# Microcontroller.net
KiCad netlist of a schematic drawn in Altium Designer
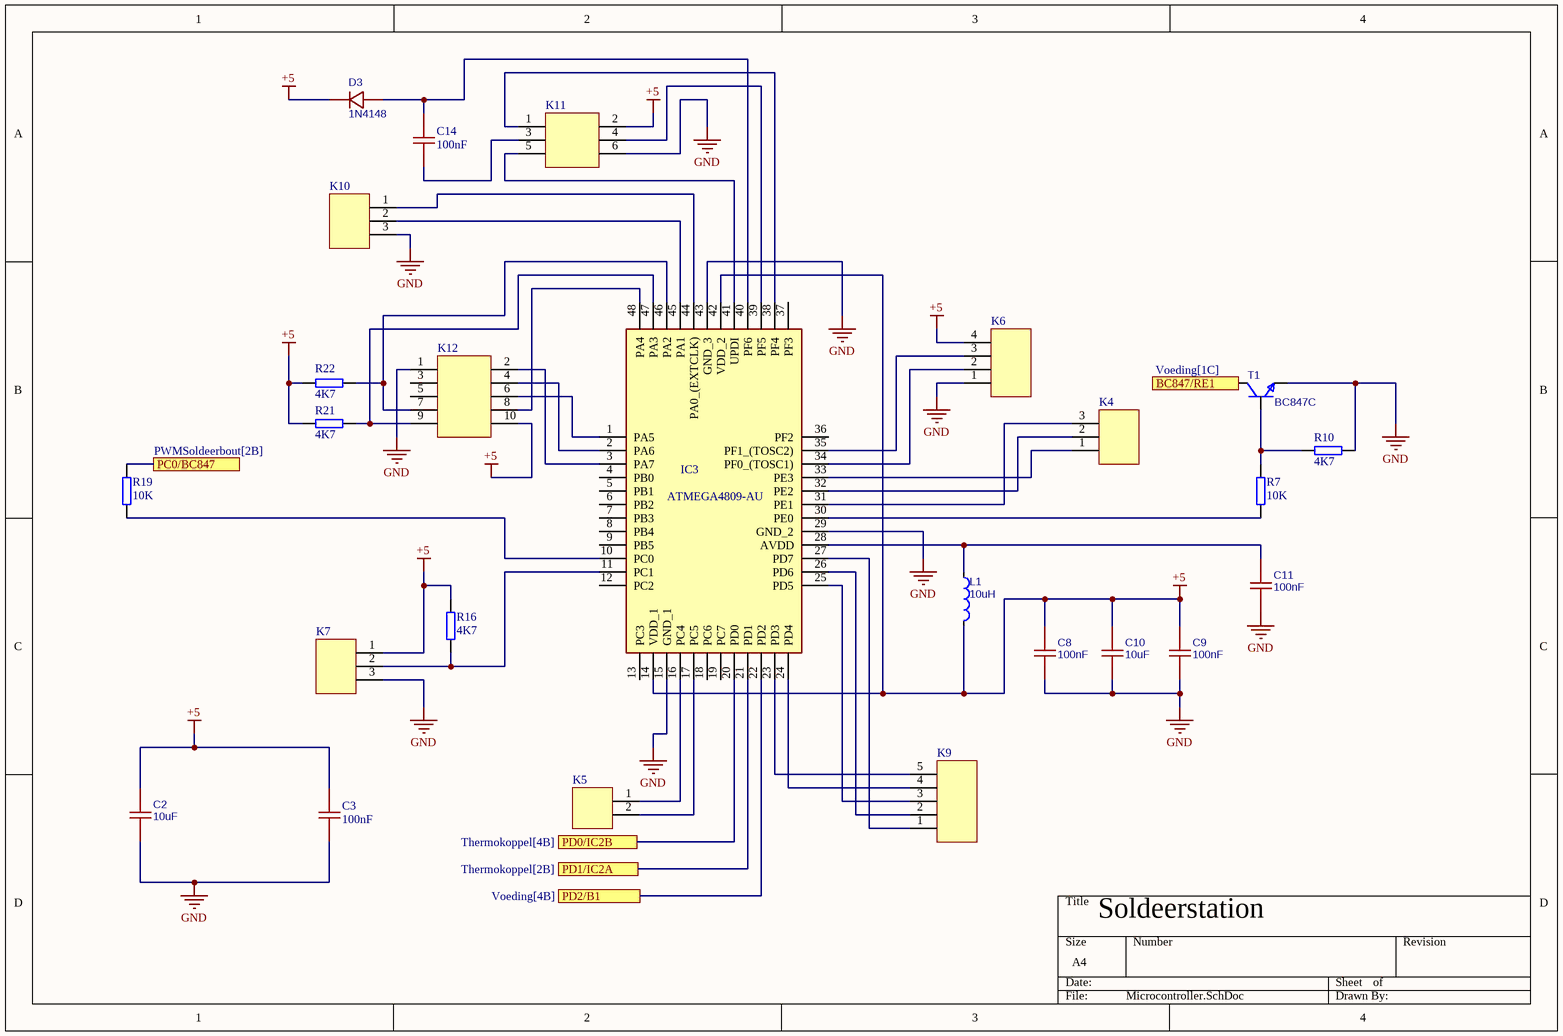
[diagram p0: Microcontroller.SchDoc]

(export (version "E")
  (design (tool "Eeschema 10.0.6"))
  (components
    (comp (ref "C2")
      (value "10uF")
      (footprint "C2,5,10 10uF")
      (fields
        (field (name "BOM_SUPPLIER PART") "C440198")
        (field (name "BOM_MANUFACTURER PART") "GRM21BR61H106KE43L")
        (field (name "CONTRIBUTOR") "LCSC")
      )
      (libsource (lib "SoldeerStation") (part "C2,5,10 10uF"))
    )
    (comp (ref "C3")
      (value "100nF")
      (footprint "C6,7,12,13 10nF")
      (libsource (lib "SoldeerStation") (part "C 100nF"))
    )
    (comp (ref "C8")
      (value "100nF")
      (footprint "C6,7,12,13 10nF")
      (fields
        (field (name "BOM_SUPPLIER PART") "C376921")
        (field (name "BOM_MANUFACTURER PART") "TCC0805X7R103M500DT")
        (field (name "CONTRIBUTOR") "LCSC")
      )
      (libsource (lib "SoldeerStation") (part "C6,7,12,13 10nF"))
    )
    (comp (ref "C9")
      (value "100nF")
      (footprint "C6,7,12,13 10nF")
      (fields
        (field (name "BOM_SUPPLIER PART") "C376921")
        (field (name "BOM_MANUFACTURER PART") "TCC0805X7R103M500DT")
        (field (name "CONTRIBUTOR") "LCSC")
      )
      (libsource (lib "SoldeerStation") (part "C6,7,12,13 10nF"))
    )
    (comp (ref "C10")
      (value "10uF")
      (footprint "C2,5,10 10uF")
      (fields
        (field (name "BOM_SUPPLIER PART") "C440198")
        (field (name "BOM_MANUFACTURER PART") "GRM21BR61H106KE43L")
        (field (name "CONTRIBUTOR") "LCSC")
      )
      (libsource (lib "SoldeerStation") (part "C2,5,10 10uF"))
    )
    (comp (ref "C11")
      (value "100nF")
      (footprint "C6,7,12,13 10nF")
      (fields
        (field (name "BOM_SUPPLIER PART") "C376921")
        (field (name "BOM_MANUFACTURER PART") "TCC0805X7R103M500DT")
        (field (name "CONTRIBUTOR") "LCSC")
      )
      (libsource (lib "SoldeerStation") (part "C6,7,12,13 10nF"))
    )
    (comp (ref "C14")
      (value "100nF")
      (footprint "C6,7,12,13 10nF")
      (libsource (lib "SoldeerStation") (part "C 100nF"))
    )
    (comp (ref "D3")
      (value "1N4148")
      (footprint "D3 1N14148")
      (description "1N4148W-C84367")
      (fields (field (name "BOM_MANUFACTURER PART") "1N4148W") (field (name "BOM_SUPPLIER PART") "C84367"))
      (libsource (lib "SoldeerStation") (part "D3 1N14148"))
    )
    (comp (ref "IC3")
      (value "ATMEGA4809-AU")
      (footprint "IC3 ATMEGA4809-AU")
      (description "8-bit Microcontrollers - MCU 20MHz, 48KB, TQFP")
      (fields (field (name "MOUSER PART NUMBER") "556-ATMEGA4809-AU"))
      (libsource (lib "SoldeerStation") (part "IC3 ATMEGA4809-AU"))
    )
    (comp (ref "K4") (value "~") (footprint "PInHeader_3") (libsource (lib "") (part "K PinHeader_3_1")))
    (comp (ref "K5")
      (value "~")
      (footprint "PInHeader_2")
      (libsource (lib "SoldeerStation") (part "K PinHeader_2"))
    )
    (comp (ref "K6")
      (value "~")
      (footprint "PInHeader_4")
      (libsource (lib "SoldeerStation") (part "K PinHeader_4"))
    )
    (comp (ref "K7")
      (value "~")
      (footprint "PInHeader_3")
      (libsource (lib "SoldeerStation") (part "K PinHeader_3"))
    )
    (comp (ref "K9")
      (value "~")
      (footprint "PInHeader_5")
      (libsource (lib "SoldeerStation") (part "K PinHeader_5"))
    )
    (comp (ref "K10")
      (value "~")
      (footprint "PInHeader_3")
      (libsource (lib "SoldeerStation") (part "K PinHeader_3"))
    )
    (comp (ref "K11")
      (value "~")
      (footprint "PInHeader_6")
      (libsource (lib "SoldeerStation") (part "K PinHeader_6"))
    )
    (comp (ref "K12")
      (value "~")
      (footprint "BOxHeader_10")
      (libsource (lib "SoldeerStation") (part "K Boxheader_10"))
    )
    (comp (ref "L1")
      (value "10uH")
      (footprint "L2 SmoorSpoel")
      (fields
        (field (name "BOM_SUPPLIER PART") "C2922559")
        (field (name "BOM_MANUFACTURER PART") "PMI201214S-100M")
        (field (name "CONTRIBUTOR") "LCSC")
      )
      (libsource (lib "SoldeerStation") (part "L2 smoorspoel"))
    )
    (comp (ref "R7")
      (value "10K")
      (footprint "RESC2013X50X30ML20T20")
      (fields (field (name "MANUFACTURER") "Vishay Dale") (field (name "PART NUMBER") "CRCW08050000Z0EA"))
      (libsource (lib "SoldeerStation") (part "R Resistor"))
    )
    (comp (ref "R10")
      (value "4K7")
      (footprint "RESC2013X50X30ML20T20")
      (fields (field (name "MANUFACTURER") "Vishay Dale") (field (name "PART NUMBER") "CRCW08050000Z0EA"))
      (libsource (lib "SoldeerStation") (part "R Resistor"))
    )
    (comp (ref "R16")
      (value "4K7")
      (footprint "RESC2013X50X30ML20T20")
      (fields (field (name "MANUFACTURER") "Vishay Dale") (field (name "PART NUMBER") "CRCW08050000Z0EA"))
      (libsource (lib "SoldeerStation") (part "R Resistor"))
    )
    (comp (ref "R19")
      (value "10K")
      (footprint "RESC2013X50X30ML20T20")
      (fields (field (name "MANUFACTURER") "Vishay Dale") (field (name "PART NUMBER") "CRCW08050000Z0EA"))
      (libsource (lib "SoldeerStation") (part "R Resistor"))
    )
    (comp (ref "R21")
      (value "4K7")
      (footprint "RESC2013X50X30ML20T20")
      (fields (field (name "MANUFACTURER") "Vishay Dale") (field (name "PART NUMBER") "CRCW08050000Z0EA"))
      (libsource (lib "SoldeerStation") (part "R Resistor"))
    )
    (comp (ref "R22")
      (value "4K7")
      (footprint "RESC2013X50X30ML20T20")
      (fields (field (name "MANUFACTURER") "Vishay Dale") (field (name "PART NUMBER") "CRCW08050000Z0EA"))
      (libsource (lib "SoldeerStation") (part "R Resistor"))
    )
    (comp (ref "T1")
      (value "BC847C")
      (footprint "T1,2,4 Bipolar Transistors")
      (description "BC847C_C3027113")
      (fields (field (name "BOM_SUPPLIER PART") "C3027113") (field (name "CONTRIBUTOR") "lcsc"))
      (libsource (lib "SoldeerStation") (part "T1,2,4 transisitors"))
    )
  )
  (nets
    (net (code "1") (name "+5") (class "Default")
      (node (ref "C10") (pin "2") (pinfunction "2_2") (pintype "passive"))
      (node (ref "C2") (pin "2") (pinfunction "2_2") (pintype "passive"))
      (node (ref "C3") (pin "2") (pinfunction "2_2") (pintype "passive"))
      (node (ref "C8") (pin "1") (pinfunction "1_1") (pintype "passive"))
      (node (ref "C9") (pin "1") (pinfunction "1_1") (pintype "passive"))
      (node (ref "D3") (pin "1") (pinfunction "C_1") (pintype "passive"))
      (node (ref "IC3") (pin "14") (pinfunction "VDD_1_14") (pintype "passive"))
      (node (ref "IC3") (pin "42") (pinfunction "VDD_2_42") (pintype "passive"))
      (node (ref "K11") (pin "2") (pintype "passive"))
      (node (ref "K12") (pin "10") (pintype "passive"))
      (node (ref "K6") (pin "4") (pintype "passive"))
      (node (ref "K7") (pin "1") (pintype "passive"))
      (node (ref "L1") (pin "2") (pinfunction "2_2") (pintype "passive"))
      (node (ref "R16") (pin "2") (pinfunction "2_2") (pintype "passive"))
      (node (ref "R21") (pin "1") (pinfunction "1_1") (pintype "passive"))
      (node (ref "R22") (pin "1") (pinfunction "1_1") (pintype "passive"))
    )
    (net (code "3") (name "/PC0{slash}BC847") (class "Default")
      (node (ref "R19") (pin "2") (pinfunction "2_2") (pintype "passive"))
    )
    (net (code "4") (name "/PD0{slash}IC2B") (class "Default")
      (node (ref "IC3") (pin "20") (pinfunction "PD0_20") (pintype "passive"))
    )
    (net (code "5") (name "/PD1{slash}IC2A") (class "Default")
      (node (ref "IC3") (pin "21") (pinfunction "PD1_21") (pintype "passive"))
    )
    (net (code "6") (name "/PD2{slash}B1") (class "Default")
      (node (ref "IC3") (pin "22") (pinfunction "PD2_22") (pintype "passive"))
    )
    (net (code "7") (name "GND") (class "Default")
      (node (ref "C10") (pin "1") (pinfunction "1_1") (pintype "passive"))
      (node (ref "C11") (pin "2") (pinfunction "2_2") (pintype "passive"))
      (node (ref "C2") (pin "1") (pinfunction "1_1") (pintype "passive"))
      (node (ref "C3") (pin "1") (pinfunction "1_1") (pintype "passive"))
      (node (ref "C8") (pin "2") (pinfunction "2_2") (pintype "passive"))
      (node (ref "C9") (pin "2") (pinfunction "2_2") (pintype "passive"))
      (node (ref "IC3") (pin "15") (pinfunction "GND_1_15") (pintype "passive"))
      (node (ref "IC3") (pin "29") (pinfunction "GND_2_29") (pintype "passive"))
      (node (ref "IC3") (pin "43") (pinfunction "GND_3_43") (pintype "passive"))
      (node (ref "K10") (pin "3") (pintype "passive"))
      (node (ref "K11") (pin "6") (pintype "passive"))
      (node (ref "K12") (pin "1") (pintype "passive"))
      (node (ref "K6") (pin "1") (pintype "passive"))
      (node (ref "K7") (pin "3") (pintype "passive"))
      (node (ref "R10") (pin "2") (pinfunction "2_2") (pintype "passive"))
      (node (ref "T1") (pin "2") (pinfunction "E_2") (pintype "passive"))
    )
    (net (code "8") (name "Net-(C14-Pad1)") (class "Default")
      (node (ref "C14") (pin "1") (pinfunction "1_1") (pintype "passive"))
      (node (ref "K11") (pin "3") (pintype "passive"))
    )
    (net (code "9") (name "Net-(D3-A)") (class "Default")
      (node (ref "C14") (pin "2") (pinfunction "2_2") (pintype "passive"))
      (node (ref "D3") (pin "2") (pinfunction "A_2") (pintype "passive"))
      (node (ref "IC3") (pin "40") (pinfunction "PF6_40") (pintype "passive"))
    )
    (net (code "10") (name "Net-(IC3-AVDD)") (class "Default")
      (node (ref "C11") (pin "1") (pinfunction "1_1") (pintype "passive"))
      (node (ref "IC3") (pin "28") (pinfunction "AVDD_28") (pintype "passive"))
      (node (ref "L1") (pin "1") (pinfunction "1_1") (pintype "passive"))
    )
    (net (code "11") (name "Net-(IC3-PA0_(EXTCLK))") (class "Default")
      (node (ref "IC3") (pin "44") (pinfunction "PA0_(EXTCLK)_44") (pintype "passive"))
      (node (ref "K10") (pin "1") (pintype "passive"))
    )
    (net (code "12") (name "Net-(IC3-PA1)") (class "Default")
      (node (ref "IC3") (pin "45") (pinfunction "PA1_45") (pintype "passive"))
      (node (ref "K10") (pin "2") (pintype "passive"))
    )
    (net (code "13") (name "Net-(IC3-PA2)") (class "Default")
      (node (ref "IC3") (pin "46") (pinfunction "PA2_46") (pintype "passive"))
      (node (ref "K12") (pin "7") (pintype "passive"))
      (node (ref "R22") (pin "2") (pinfunction "2_2") (pintype "passive"))
    )
    (net (code "14") (name "Net-(IC3-PA3)") (class "Default")
      (node (ref "IC3") (pin "47") (pinfunction "PA3_47") (pintype "passive"))
      (node (ref "K12") (pin "9") (pintype "passive"))
      (node (ref "R21") (pin "2") (pinfunction "2_2") (pintype "passive"))
    )
    (net (code "15") (name "Net-(IC3-PA4)") (class "Default")
      (node (ref "IC3") (pin "48") (pinfunction "PA4_48") (pintype "passive"))
      (node (ref "K12") (pin "8") (pintype "passive"))
    )
    (net (code "16") (name "Net-(IC3-PA5)") (class "Default")
      (node (ref "IC3") (pin "1") (pinfunction "PA5_1") (pintype "passive"))
      (node (ref "K12") (pin "6") (pintype "passive"))
    )
    (net (code "17") (name "Net-(IC3-PA6)") (class "Default")
      (node (ref "IC3") (pin "2") (pinfunction "PA6_2") (pintype "passive"))
      (node (ref "K12") (pin "4") (pintype "passive"))
    )
    (net (code "18") (name "Net-(IC3-PA7)") (class "Default")
      (node (ref "IC3") (pin "3") (pinfunction "PA7_3") (pintype "passive"))
      (node (ref "K12") (pin "2") (pintype "passive"))
    )
    (net (code "19") (name "Net-(IC3-PC0)") (class "Default")
      (node (ref "IC3") (pin "10") (pinfunction "PC0_10") (pintype "passive"))
      (node (ref "R19") (pin "1") (pinfunction "1_1") (pintype "passive"))
    )
    (net (code "20") (name "Net-(IC3-PC1)") (class "Default")
      (node (ref "IC3") (pin "11") (pinfunction "PC1_11") (pintype "passive"))
      (node (ref "K7") (pin "2") (pintype "passive"))
      (node (ref "R16") (pin "1") (pinfunction "1_1") (pintype "passive"))
    )
    (net (code "21") (name "Net-(IC3-PC4)") (class "Default")
      (node (ref "IC3") (pin "16") (pinfunction "PC4_16") (pintype "passive"))
      (node (ref "K5") (pin "1") (pintype "passive"))
    )
    (net (code "22") (name "Net-(IC3-PC5)") (class "Default")
      (node (ref "IC3") (pin "17") (pinfunction "PC5_17") (pintype "passive"))
      (node (ref "K5") (pin "2") (pintype "passive"))
    )
    (net (code "23") (name "Net-(IC3-PD3)") (class "Default")
      (node (ref "IC3") (pin "23") (pinfunction "PD3_23") (pintype "passive"))
      (node (ref "K9") (pin "5") (pintype "passive"))
    )
    (net (code "24") (name "Net-(IC3-PD4)") (class "Default")
      (node (ref "IC3") (pin "24") (pinfunction "PD4_24") (pintype "passive"))
      (node (ref "K9") (pin "4") (pintype "passive"))
    )
    (net (code "25") (name "Net-(IC3-PD5)") (class "Default")
      (node (ref "IC3") (pin "25") (pinfunction "PD5_25") (pintype "passive"))
      (node (ref "K9") (pin "3") (pintype "passive"))
    )
    (net (code "26") (name "Net-(IC3-PD6)") (class "Default")
      (node (ref "IC3") (pin "26") (pinfunction "PD6_26") (pintype "passive"))
      (node (ref "K9") (pin "2") (pintype "passive"))
    )
    (net (code "27") (name "Net-(IC3-PD7)") (class "Default")
      (node (ref "IC3") (pin "27") (pinfunction "PD7_27") (pintype "passive"))
      (node (ref "K9") (pin "1") (pintype "passive"))
    )
    (net (code "28") (name "Net-(IC3-PE0)") (class "Default")
      (node (ref "IC3") (pin "30") (pinfunction "PE0_30") (pintype "passive"))
      (node (ref "R7") (pin "1") (pinfunction "1_1") (pintype "passive"))
    )
    (net (code "29") (name "Net-(IC3-PE1)") (class "Default")
      (node (ref "IC3") (pin "31") (pinfunction "PE1_31") (pintype "passive"))
      (node (ref "K4") (pin "3") (pintype "passive"))
    )
    (net (code "30") (name "Net-(IC3-PE2)") (class "Default")
      (node (ref "IC3") (pin "32") (pinfunction "PE2_32") (pintype "passive"))
      (node (ref "K4") (pin "2") (pintype "passive"))
    )
    (net (code "31") (name "Net-(IC3-PE3)") (class "Default")
      (node (ref "IC3") (pin "33") (pinfunction "PE3_33") (pintype "passive"))
      (node (ref "K4") (pin "1") (pintype "passive"))
    )
    (net (code "32") (name "Net-(IC3-PF0_(TOSC1))") (class "Default")
      (node (ref "IC3") (pin "34") (pinfunction "PF0_(TOSC1)_34") (pintype "passive"))
      (node (ref "K6") (pin "2") (pintype "passive"))
    )
    (net (code "33") (name "Net-(IC3-PF1_(TOSC2))") (class "Default")
      (node (ref "IC3") (pin "35") (pinfunction "PF1_(TOSC2)_35") (pintype "passive"))
      (node (ref "K6") (pin "3") (pintype "passive"))
    )
    (net (code "34") (name "Net-(IC3-PF4)") (class "Default")
      (node (ref "IC3") (pin "38") (pinfunction "PF4_38") (pintype "passive"))
      (node (ref "K11") (pin "1") (pintype "passive"))
    )
    (net (code "35") (name "Net-(IC3-PF5)") (class "Default")
      (node (ref "IC3") (pin "39") (pinfunction "PF5_39") (pintype "passive"))
      (node (ref "K11") (pin "4") (pintype "passive"))
    )
    (net (code "36") (name "Net-(IC3-UPDI)") (class "Default")
      (node (ref "IC3") (pin "41") (pinfunction "UPDI_41") (pintype "passive"))
      (node (ref "K11") (pin "5") (pintype "passive"))
    )
    (net (code "37") (name "Net-(T1-B)") (class "Default")
      (node (ref "R10") (pin "1") (pinfunction "1_1") (pintype "passive"))
      (node (ref "R7") (pin "2") (pinfunction "2_2") (pintype "passive"))
      (node (ref "T1") (pin "1") (pinfunction "B_1") (pintype "passive"))
    )
    (net (code "38") (name "unconnected-(IC3-PB0-Pad4)") (class "Default")
      (node (ref "IC3") (pin "4") (pinfunction "PB0_4") (pintype "passive"))
    )
    (net (code "39") (name "unconnected-(IC3-PB1-Pad5)") (class "Default")
      (node (ref "IC3") (pin "5") (pinfunction "PB1_5") (pintype "passive"))
    )
    (net (code "40") (name "unconnected-(IC3-PB2-Pad6)") (class "Default")
      (node (ref "IC3") (pin "6") (pinfunction "PB2_6") (pintype "passive"))
    )
    (net (code "41") (name "unconnected-(IC3-PB3-Pad7)") (class "Default")
      (node (ref "IC3") (pin "7") (pinfunction "PB3_7") (pintype "passive"))
    )
    (net (code "42") (name "unconnected-(IC3-PB4-Pad8)") (class "Default")
      (node (ref "IC3") (pin "8") (pinfunction "PB4_8") (pintype "passive"))
    )
    (net (code "43") (name "unconnected-(IC3-PB5-Pad9)") (class "Default")
      (node (ref "IC3") (pin "9") (pinfunction "PB5_9") (pintype "passive"))
    )
    (net (code "44") (name "unconnected-(IC3-PC2-Pad12)") (class "Default")
      (node (ref "IC3") (pin "12") (pinfunction "PC2_12") (pintype "passive"))
    )
    (net (code "45") (name "unconnected-(IC3-PC3-Pad13)") (class "Default")
      (node (ref "IC3") (pin "13") (pinfunction "PC3_13") (pintype "passive"))
    )
    (net (code "46") (name "unconnected-(IC3-PC6-Pad18)") (class "Default")
      (node (ref "IC3") (pin "18") (pinfunction "PC6_18") (pintype "passive"))
    )
    (net (code "47") (name "unconnected-(IC3-PC7-Pad19)") (class "Default")
      (node (ref "IC3") (pin "19") (pinfunction "PC7_19") (pintype "passive"))
    )
    (net (code "48") (name "unconnected-(IC3-PF2-Pad36)") (class "Default")
      (node (ref "IC3") (pin "36") (pinfunction "PF2_36") (pintype "passive"))
    )
    (net (code "49") (name "unconnected-(IC3-PF3-Pad37)") (class "Default")
      (node (ref "IC3") (pin "37") (pinfunction "PF3_37") (pintype "passive"))
    )
    (net (code "50") (name "unconnected-(K12-Pad3)") (class "Default")
      (node (ref "K12") (pin "3") (pintype "passive"))
    )
    (net (code "51") (name "unconnected-(K12-Pad5)") (class "Default")
      (node (ref "K12") (pin "5") (pintype "passive"))
    )
    (net (code "52") (name "unconnected-(T1-C-Pad3)") (class "Default")
      (node (ref "T1") (pin "3") (pinfunction "C_3") (pintype "passive"))
    )
  )
)
